# Control_Module_PER.net
KiCad netlist of a schematic drawn in Altium Designer
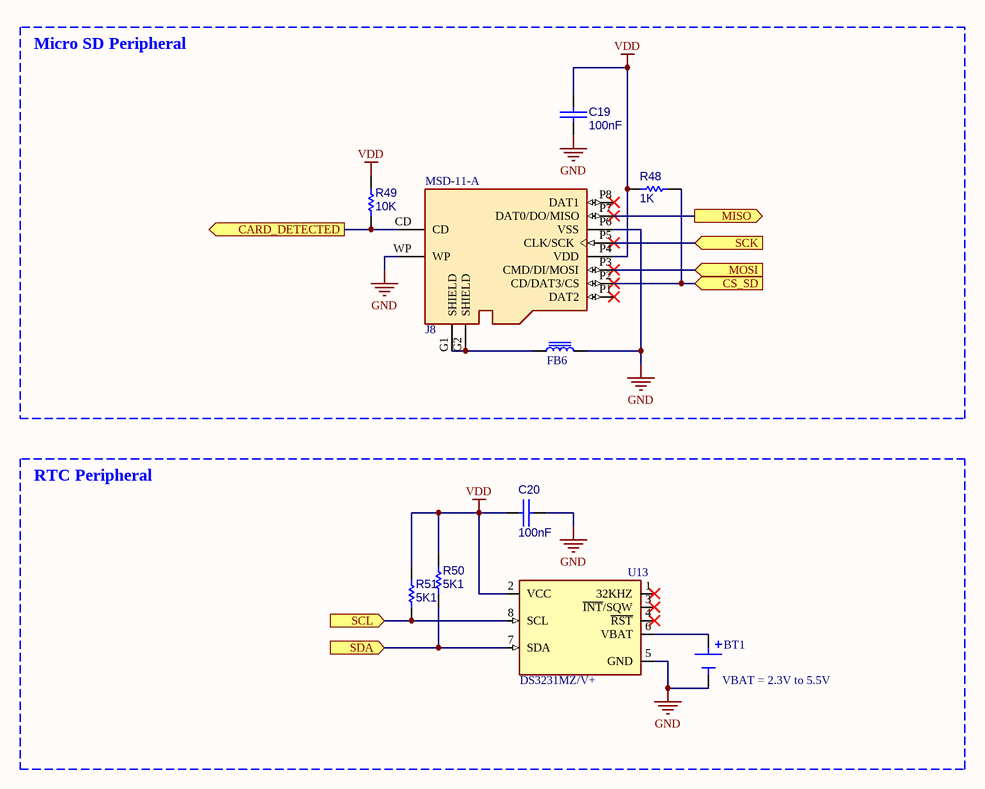
[diagram p0: Control_Module_PER.SchDoc]

(export (version "E")
  (design (tool "Eeschema 10.0.6"))
  (components
    (comp (ref "BT1")
      (value "VBAT = 2.3V to 5.5V")
      (footprint "KEYSTONE_1063TR_1063TR")
      (description "Battery Holder Coin 20 SMT Nickel T&R")
      (fields (field (name "MF") "TE Connectivity") (field (name "MP") "BAT-HLD-011-THM"))
      (libsource (lib "Control_Module_Symbols") (part "BAT-HLD-011-THM"))
    )
    (comp (ref "C19")
      (value "100nF")
      (footprint "CAP0402")
      (description "Non Polarized Capacitor")
      (libsource (lib "Control_Module_Symbols") (part "CAP"))
    )
    (comp (ref "C20")
      (value "100nF")
      (footprint "CAP0402")
      (description "Non Polarized Capacitor")
      (libsource (lib "Control_Module_Symbols") (part "CAP"))
    )
    (comp (ref "FB6")
      (value "Choke")
      (footprint "CHOKE0603")
      (description "High Frequency EMI Suppression Ferrite Bead")
      (fields
        (field (name "MANUFACTURER PART NUMBER") "742863160")
        (field (name "MANUFACTURER") "Wurth Elektronik")
      )
      (libsource (lib "Control_Module_Symbols") (part "Choke"))
    )
    (comp (ref "J8")
      (value "MSD-11-A")
      (footprint "CUI_MSD-11-A")
      (fields (field (name "MF") "Same Sky"))
      (libsource (lib "Control_Module_Symbols") (part "MSD-11-A"))
    )
    (comp (ref "R48")
      (value "1K")
      (footprint "RES0402")
      (description "Resistor")
      (libsource (lib "Control_Module_Symbols") (part "Res1"))
    )
    (comp (ref "R49")
      (value "10K")
      (footprint "RES0402")
      (description "Resistor")
      (libsource (lib "Control_Module_Symbols") (part "Res1"))
    )
    (comp (ref "R50")
      (value "5K1")
      (footprint "RES0402")
      (description "Resistor")
      (libsource (lib "Control_Module_Symbols") (part "Res1"))
    )
    (comp (ref "R51")
      (value "5K1")
      (footprint "RES0402")
      (description "Resistor")
      (libsource (lib "Control_Module_Symbols") (part "Res1"))
    )
    (comp (ref "U13")
      (value "DS3231MZ/V+")
      (footprint "21-0041B_8")
      (description "±5ppm, I2C Real-Time Clock")
      (fields (field (name "MF") "Analog Devices"))
      (libsource (lib "Control_Module_Symbols") (part "DS3231MZ/V+"))
    )
  )
  (nets
    (net (code "1") (name "/CARD_DETECTED") (class "Default")
      (node (ref "J8") (pin "CD") (pinfunction "CD_CD") (pintype "passive"))
      (node (ref "R49") (pin "2") (pinfunction "2_2") (pintype "passive"))
    )
    (net (code "2") (name "/CS_SD") (class "Default")
      (node (ref "J8") (pin "P2") (pinfunction "CD/DAT3/CS_P2") (pintype "bidirectional"))
      (node (ref "R48") (pin "2") (pinfunction "2_2") (pintype "passive"))
    )
    (net (code "3") (name "/MISO") (class "Default")
      (node (ref "J8") (pin "P7") (pinfunction "DAT0/DO/MISO_P7") (pintype "bidirectional+no_connect"))
    )
    (net (code "4") (name "/MOSI") (class "Default")
      (node (ref "J8") (pin "P3") (pinfunction "CMD/DI/MOSI_P3") (pintype "bidirectional+no_connect"))
    )
    (net (code "5") (name "/SCK") (class "Default")
      (node (ref "J8") (pin "P5") (pinfunction "CLK/SCK_P5") (pintype "input+no_connect"))
    )
    (net (code "6") (name "/SCL") (class "Default")
      (node (ref "R51") (pin "2") (pinfunction "2_2") (pintype "passive"))
      (node (ref "U13") (pin "8") (pinfunction "SCL_8") (pintype "input"))
    )
    (net (code "7") (name "/SDA") (class "Default")
      (node (ref "R50") (pin "2") (pinfunction "2_2") (pintype "passive"))
      (node (ref "U13") (pin "7") (pinfunction "SDA_7") (pintype "input"))
    )
    (net (code "8") (name "GND") (class "Default")
      (node (ref "BT1") (pin "N") (pinfunction "N_N") (pintype "passive"))
      (node (ref "C19") (pin "2") (pinfunction "2_2") (pintype "passive"))
      (node (ref "C20") (pin "2") (pinfunction "2_2") (pintype "passive"))
      (node (ref "FB6") (pin "2") (pinfunction "2_2") (pintype "passive"))
      (node (ref "J8") (pin "P6") (pinfunction "VSS_P6") (pintype "power_in"))
      (node (ref "J8") (pin "WP") (pinfunction "WP_WP") (pintype "passive"))
      (node (ref "U13") (pin "5") (pinfunction "GND_5") (pintype "power_in"))
    )
    (net (code "9") (name "Net-(FB6-Pad1)") (class "Default")
      (node (ref "FB6") (pin "1") (pinfunction "1_1") (pintype "passive"))
      (node (ref "J8") (pin "G1") (pinfunction "SHIELD_G1") (pintype "power_in"))
      (node (ref "J8") (pin "G2") (pinfunction "SHIELD_G2") (pintype "power_in"))
    )
    (net (code "10") (name "Net-(U13-VBAT)") (class "Default")
      (node (ref "BT1") (pin "P") (pinfunction "P_P") (pintype "passive"))
      (node (ref "U13") (pin "6") (pinfunction "VBAT_6") (pintype "power_in"))
    )
    (net (code "11") (name "VDD") (class "Default")
      (node (ref "C19") (pin "1") (pinfunction "1_1") (pintype "passive"))
      (node (ref "C20") (pin "1") (pinfunction "1_1") (pintype "passive"))
      (node (ref "J8") (pin "P4") (pinfunction "VDD_P4") (pintype "power_in"))
      (node (ref "R48") (pin "1") (pinfunction "1_1") (pintype "passive"))
      (node (ref "R49") (pin "1") (pinfunction "1_1") (pintype "passive"))
      (node (ref "R50") (pin "1") (pinfunction "1_1") (pintype "passive"))
      (node (ref "R51") (pin "1") (pinfunction "1_1") (pintype "passive"))
      (node (ref "U13") (pin "2") (pinfunction "VCC_2") (pintype "power_in"))
    )
    (net (code "12") (name "unconnected-(J8-DAT1-PadP8)") (class "Default")
      (node (ref "J8") (pin "P8") (pinfunction "DAT1_P8") (pintype "bidirectional+no_connect"))
    )
    (net (code "13") (name "unconnected-(J8-DAT2-PadP1)") (class "Default")
      (node (ref "J8") (pin "P1") (pinfunction "DAT2_P1") (pintype "bidirectional+no_connect"))
    )
    (net (code "14") (name "unconnected-(U13-32KHZ-Pad1)") (class "Default")
      (node (ref "U13") (pin "1") (pinfunction "32KHZ_1") (pintype "passive+no_connect"))
    )
    (net (code "15") (name "unconnected-(U13-~{INT}{slash}SQW-Pad3)") (class "Default")
      (node (ref "U13") (pin "3") (pinfunction "~{INT}/SQW_3") (pintype "passive+no_connect"))
    )
    (net (code "16") (name "unconnected-(U13-~{RST}-Pad4)") (class "Default")
      (node (ref "U13") (pin "4") (pinfunction "~{RST}_4") (pintype "passive+no_connect"))
    )
  )
)
